# chronos-core.net
KiCad netlist of a schematic drawn in Altium Designer
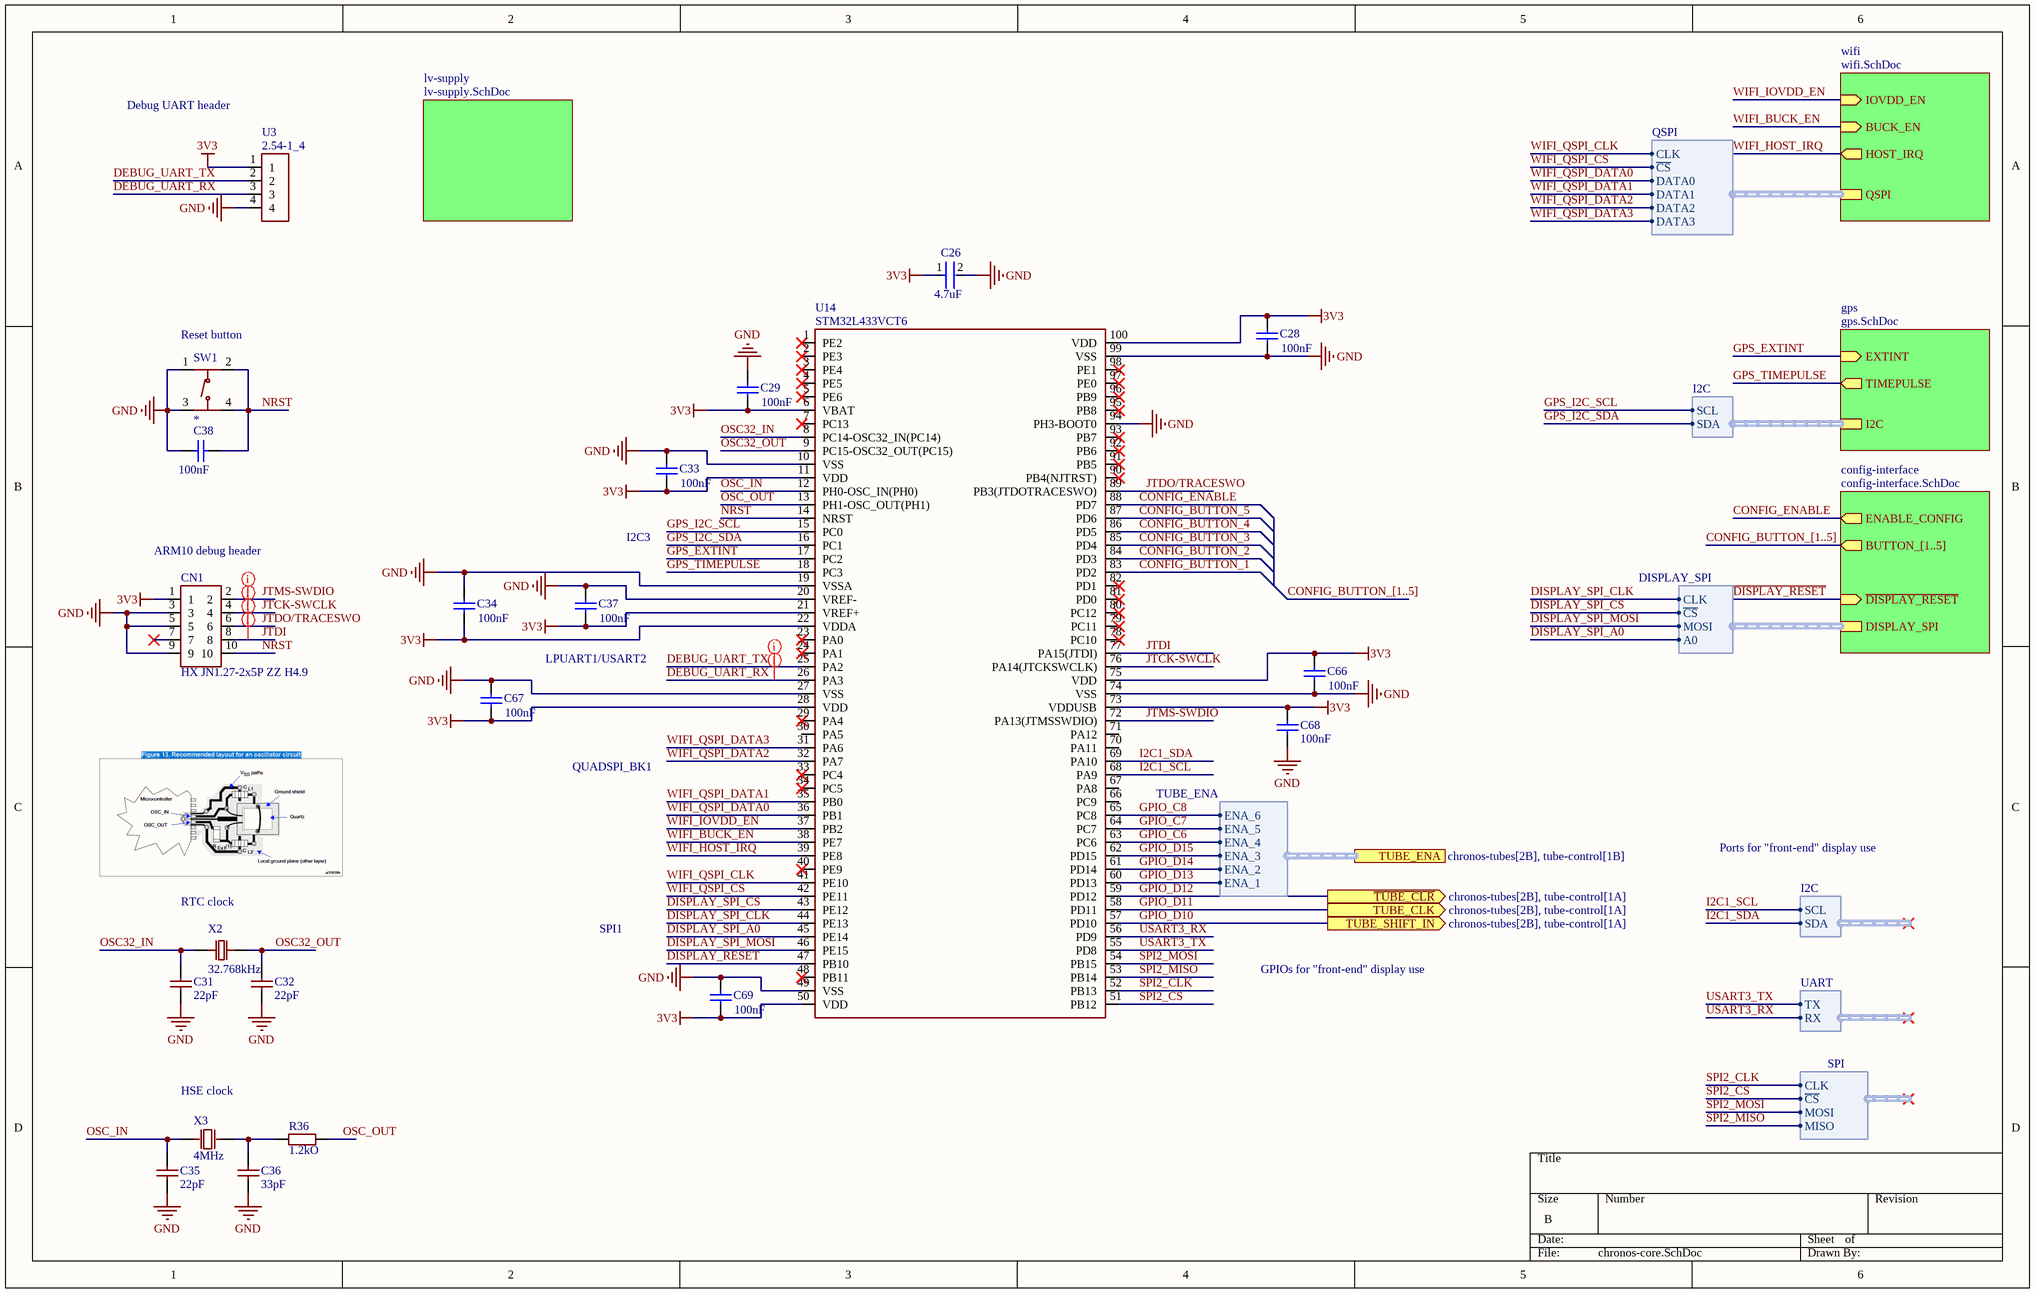
[diagram p0: chronos-core.SchDoc]

(export (version "E")
  (design (tool "Eeschema 10.0.6"))
  (components
    (comp (ref "C26")
      (value "CL05A475MP5NRNC")
      (footprint "FP-CL282-IPC_C")
      (description "Cap Ceramic 4.7uF 10V X5R ±20% SMD 0402 +85°C Paper T/R")
      (fields (field (name "CAPACITANCE") "4.7uF") (field (name "TOLERANCE") "20%"))
      (libsource (lib "Altium Content Vault") (part "b4654b650e69147ec39a6b967a45e02"))
    )
    (comp (ref "C28")
      (value "CL05B104KO5NNNC")
      (footprint "CAPC1050X55X23ML05T13")
      (description "Chip Capacitor, 100 nF, +/- 10%, 16 V, -55 to 125 degC, 0402 (1005 Metric), RoHS, Tape and Reel")
      (fields (field (name "MANUFACTURER") "Samsung Electro-Mechanics") (field (name "CAPACITANCE") "100nF"))
      (libsource (lib "Altium Content Vault") (part "CAP-NP-2"))
    )
    (comp (ref "C29")
      (value "CL05B104KO5NNNC")
      (footprint "CAPC1050X55X23ML05T13")
      (description "Chip Capacitor, 100 nF, +/- 10%, 16 V, -55 to 125 degC, 0402 (1005 Metric), RoHS, Tape and Reel")
      (fields (field (name "MANUFACTURER") "Samsung Electro-Mechanics") (field (name "CAPACITANCE") "100nF"))
      (libsource (lib "Altium Content Vault") (part "CAP-NP-2"))
    )
    (comp (ref "C31")
      (value "22pF")
      (footprint "0402CG220J500NT")
      (fields
        (field (name "JLCPCB PART #") "C1555")
        (field (name "MANUFACTURER PART NUMBER") "0402CG220J500NT")
        (field (name "MANUFACTURER") "FH (Guangdong Fenghua Advanced Tech)")
      )
      (libsource (lib "0402CG220J500NT") (part "0402CG220J500NT"))
    )
    (comp (ref "C32")
      (value "22pF")
      (footprint "0402CG220J500NT")
      (fields
        (field (name "JLCPCB PART #") "C1555")
        (field (name "MANUFACTURER PART NUMBER") "0402CG220J500NT")
        (field (name "MANUFACTURER") "FH (Guangdong Fenghua Advanced Tech)")
      )
      (libsource (lib "0402CG220J500NT") (part "0402CG220J500NT"))
    )
    (comp (ref "C33")
      (value "CL05B104KO5NNNC")
      (footprint "CAPC1050X55X23ML05T13")
      (description "Chip Capacitor, 100 nF, +/- 10%, 16 V, -55 to 125 degC, 0402 (1005 Metric), RoHS, Tape and Reel")
      (fields (field (name "MANUFACTURER") "Samsung Electro-Mechanics") (field (name "CAPACITANCE") "100nF"))
      (libsource (lib "Altium Content Vault") (part "CAP-NP-2"))
    )
    (comp (ref "C34")
      (value "CL05B104KO5NNNC")
      (footprint "CAPC1050X55X23ML05T13")
      (description "Chip Capacitor, 100 nF, +/- 10%, 16 V, -55 to 125 degC, 0402 (1005 Metric), RoHS, Tape and Reel")
      (fields (field (name "MANUFACTURER") "Samsung Electro-Mechanics") (field (name "CAPACITANCE") "100nF"))
      (libsource (lib "Altium Content Vault") (part "CAP-NP-2"))
    )
    (comp (ref "C35")
      (value "22pF")
      (footprint "0402CG220J500NT")
      (fields
        (field (name "JLCPCB PART #") "C1555")
        (field (name "MANUFACTURER PART NUMBER") "0402CG220J500NT")
        (field (name "MANUFACTURER") "FH (Guangdong Fenghua Advanced Tech)")
      )
      (libsource (lib "0402CG220J500NT") (part "0402CG220J500NT"))
    )
    (comp (ref "C36")
      (value "33pF")
      (footprint "0402CG330J500NT")
      (fields
        (field (name "JLCPCB PART #") "C1562")
        (field (name "MANUFACTURER PART NUMBER") "0402CG330J500NT")
        (field (name "MANUFACTURER") "FH (Guangdong Fenghua Advanced Tech)")
      )
      (libsource (lib "0402CG330J500NT") (part "0402CG330J500NT"))
    )
    (comp (ref "C37")
      (value "CL05B104KO5NNNC")
      (footprint "CAPC1050X55X23ML05T13")
      (description "Chip Capacitor, 100 nF, +/- 10%, 16 V, -55 to 125 degC, 0402 (1005 Metric), RoHS, Tape and Reel")
      (fields (field (name "MANUFACTURER") "Samsung Electro-Mechanics") (field (name "CAPACITANCE") "100nF"))
      (libsource (lib "Altium Content Vault") (part "CAP-NP-2"))
    )
    (comp (ref "C38")
      (value "CL05B104KO5NNNC")
      (footprint "CAPC1050X55X23ML05T13")
      (description "Chip Capacitor, 100 nF, +/- 10%, 16 V, -55 to 125 degC, 0402 (1005 Metric), RoHS, Tape and Reel")
      (fields (field (name "MANUFACTURER") "Samsung Electro-Mechanics") (field (name "CAPACITANCE") "100nF"))
      (libsource (lib "Altium Content Vault") (part "CAP-NP-2"))
    )
    (comp (ref "C66")
      (value "CL05B104KO5NNNC")
      (footprint "CAPC1050X55X23ML05T13")
      (description "Chip Capacitor, 100 nF, +/- 10%, 16 V, -55 to 125 degC, 0402 (1005 Metric), RoHS, Tape and Reel")
      (fields (field (name "MANUFACTURER") "Samsung Electro-Mechanics") (field (name "CAPACITANCE") "100nF"))
      (libsource (lib "Altium Content Vault") (part "CAP-NP-2"))
    )
    (comp (ref "C67")
      (value "CL05B104KO5NNNC")
      (footprint "CAPC1050X55X23ML05T13")
      (description "Chip Capacitor, 100 nF, +/- 10%, 16 V, -55 to 125 degC, 0402 (1005 Metric), RoHS, Tape and Reel")
      (fields (field (name "MANUFACTURER") "Samsung Electro-Mechanics") (field (name "CAPACITANCE") "100nF"))
      (libsource (lib "Altium Content Vault") (part "CAP-NP-2"))
    )
    (comp (ref "C68")
      (value "CL05B104KO5NNNC")
      (footprint "CAPC1050X55X23ML05T13")
      (description "Chip Capacitor, 100 nF, +/- 10%, 16 V, -55 to 125 degC, 0402 (1005 Metric), RoHS, Tape and Reel")
      (fields (field (name "MANUFACTURER") "Samsung Electro-Mechanics") (field (name "CAPACITANCE") "100nF"))
      (libsource (lib "Altium Content Vault") (part "CAP-NP-2"))
    )
    (comp (ref "C69")
      (value "CL05B104KO5NNNC")
      (footprint "CAPC1050X55X23ML05T13")
      (description "Chip Capacitor, 100 nF, +/- 10%, 16 V, -55 to 125 degC, 0402 (1005 Metric), RoHS, Tape and Reel")
      (fields (field (name "MANUFACTURER") "Samsung Electro-Mechanics") (field (name "CAPACITANCE") "100nF"))
      (libsource (lib "Altium Content Vault") (part "CAP-NP-2"))
    )
    (comp (ref "CN1")
      (value "HX JN1.27-2x5P ZZ H4.9")
      (footprint "HX JN1.27-2x5P ZZ H4.9")
      (fields (field (name "JLCPCB PART #") "C42372547") (field (name "MANUFACTURER") "hanxia"))
      (libsource (lib "HX JN1.27-2x5P ZZ H4.9") (part "HX JN1.27-2x5P ZZ H4.9"))
    )
    (comp (ref "R36")
      (value "1.2kO")
      (footprint "0402WGF1201TCE")
      (fields
        (field (name "JLCPCB PART #") "C25862")
        (field (name "MANUFACTURER PART NUMBER") "0402WGF1201TCE")
        (field (name "MANUFACTURER") "UNI-ROYAL(Uniroyal Elec)")
      )
      (libsource (lib "0402WGF1201TCE") (part "0402WGF1201TCE"))
    )
    (comp (ref "SW1")
      (value "TS-1187A-B-A-B")
      (footprint "TS-1187A-B-A-B")
      (fields
        (field (name "ALTIUM_VALUE") "*")
        (field (name "JLCPCB PART #") "C318884")
        (field (name "MANUFACTURER") "XKB Connection")
      )
      (libsource (lib "TS-1187A-B-A-B") (part "TS-1187A-B-A-B"))
    )
    (comp (ref "U3")
      (value "2.54-1_4")
      (footprint "2.54-1_4")
      (fields
        (field (name "JLCPCB PART #") "C5116483")
        (field (name "MANUFACTURER PART NUMBER") "2.54-1*4")
        (field (name "MANUFACTURER") "ZHOURI")
      )
      (libsource (lib "2.54-1_4") (part "2.54-1_4"))
    )
    (comp (ref "U14")
      (value "STM32L433VCT6")
      (footprint "STM32L433VCT6")
      (fields (field (name "JLCPCB PART #") "C915966") (field (name "MANUFACTURER") "STMicroelectronics"))
      (libsource (lib "STM32L433VCT6") (part "STM32L433VCT6"))
    )
    (comp (ref "X2")
      (value "32.768kHz")
      (footprint "Q13FC13500004")
      (description "Crystals. -40C~+85C 12.5pF 32.768kHz 70kohm Crystal Oscillator +/-20ppm SMD3215-2P Crystals ROHS")
      (fields
        (field (name "JLCPCB PART #") "C32346")
        (field (name "MANUFACTURER PART NUMBER") "Q13FC13500004")
      )
      (libsource (lib "Q13FC13500004") (part "Q13FC13500004"))
    )
    (comp (ref "X3")
      (value "4MHz")
      (footprint "X49SM4MSD2SC")
      (description "Crystals. -20C~+70C 120ohm 20pF 4MHz Crystal Oscillator +/-20ppm +/-30ppm HC-49S-SMD Crystals ROHS")
      (fields
        (field (name "JLCPCB PART #") "C13774")
        (field (name "MANUFACTURER PART NUMBER") "X49SM4MSD2SC")
      )
      (libsource (lib "X49SM4MSD2SC") (part "X49SM4MSD2SC"))
    )
  )
  (nets
    (net (code "7") (name "/CONFIG_BUTTON_1") (class "Default")
      (node (ref "U14") (pin "83") (pinfunction "PD2_83") (pintype "passive"))
    )
    (net (code "8") (name "/CONFIG_BUTTON_2") (class "Default")
      (node (ref "U14") (pin "84") (pinfunction "PD3_84") (pintype "passive"))
    )
    (net (code "9") (name "/CONFIG_BUTTON_3") (class "Default")
      (node (ref "U14") (pin "85") (pinfunction "PD4_85") (pintype "passive"))
    )
    (net (code "10") (name "/CONFIG_BUTTON_4") (class "Default")
      (node (ref "U14") (pin "86") (pinfunction "PD5_86") (pintype "passive"))
    )
    (net (code "11") (name "/CONFIG_BUTTON_5") (class "Default")
      (node (ref "U14") (pin "87") (pinfunction "PD6_87") (pintype "passive"))
    )
    (net (code "13") (name "/CONFIG_ENABLE") (class "Default")
      (node (ref "U14") (pin "88") (pinfunction "PD7_88") (pintype "passive"))
    )
    (net (code "14") (name "/DEBUG_UART_RX") (class "Default")
      (node (ref "U14") (pin "26") (pinfunction "PA3_26") (pintype "passive"))
      (node (ref "U3") (pin "3") (pinfunction "3_3") (pintype "passive"))
    )
    (net (code "15") (name "/DEBUG_UART_TX") (class "Default")
      (node (ref "U14") (pin "25") (pinfunction "PA2_25") (pintype "passive"))
      (node (ref "U3") (pin "2") (pinfunction "2_2") (pintype "passive"))
    )
    (net (code "16") (name "/DISPLAY_RESET") (class "Default")
      (node (ref "U14") (pin "47") (pinfunction "PB10_47") (pintype "passive"))
    )
    (net (code "17") (name "/DISPLAY_SPI_A0") (class "Default")
      (node (ref "U14") (pin "45") (pinfunction "PE14_45") (pintype "passive"))
    )
    (net (code "18") (name "/DISPLAY_SPI_CLK") (class "Default")
      (node (ref "U14") (pin "44") (pinfunction "PE13_44") (pintype "passive"))
    )
    (net (code "19") (name "/DISPLAY_SPI_CS") (class "Default")
      (node (ref "U14") (pin "43") (pinfunction "PE12_43") (pintype "passive"))
    )
    (net (code "20") (name "/DISPLAY_SPI_MOSI") (class "Default")
      (node (ref "U14") (pin "46") (pinfunction "PE15_46") (pintype "passive"))
    )
    (net (code "21") (name "/GPIO_C6") (class "Default")
      (node (ref "U14") (pin "63") (pinfunction "PC6_63") (pintype "passive"))
    )
    (net (code "22") (name "/GPIO_C7") (class "Default")
      (node (ref "U14") (pin "64") (pinfunction "PC7_64") (pintype "passive"))
    )
    (net (code "23") (name "/GPIO_C8") (class "Default")
      (node (ref "U14") (pin "65") (pinfunction "PC8_65") (pintype "passive"))
    )
    (net (code "24") (name "/GPIO_D10") (class "Default")
      (node (ref "U14") (pin "57") (pinfunction "PD10_57") (pintype "passive"))
    )
    (net (code "25") (name "/GPIO_D11") (class "Default")
      (node (ref "U14") (pin "58") (pinfunction "PD11_58") (pintype "passive"))
    )
    (net (code "26") (name "/GPIO_D12") (class "Default")
      (node (ref "U14") (pin "59") (pinfunction "PD12_59") (pintype "passive"))
    )
    (net (code "27") (name "/GPIO_D13") (class "Default")
      (node (ref "U14") (pin "60") (pinfunction "PD13_60") (pintype "passive"))
    )
    (net (code "28") (name "/GPIO_D14") (class "Default")
      (node (ref "U14") (pin "61") (pinfunction "PD14_61") (pintype "passive"))
    )
    (net (code "29") (name "/GPIO_D15") (class "Default")
      (node (ref "U14") (pin "62") (pinfunction "PD15_62") (pintype "passive"))
    )
    (net (code "30") (name "/GPS_EXTINT") (class "Default")
      (node (ref "U14") (pin "17") (pinfunction "PC2_17") (pintype "passive"))
    )
    (net (code "31") (name "/GPS_I2C_SCL") (class "Default")
      (node (ref "U14") (pin "15") (pinfunction "PC0_15") (pintype "passive"))
    )
    (net (code "32") (name "/GPS_I2C_SDA") (class "Default")
      (node (ref "U14") (pin "16") (pinfunction "PC1_16") (pintype "passive"))
    )
    (net (code "33") (name "/GPS_TIMEPULSE") (class "Default")
      (node (ref "U14") (pin "18") (pinfunction "PC3_18") (pintype "passive"))
    )
    (net (code "34") (name "/I2C1_SCL") (class "Default")
      (node (ref "U14") (pin "68") (pinfunction "PA9_68") (pintype "passive"))
    )
    (net (code "35") (name "/I2C1_SDA") (class "Default")
      (node (ref "U14") (pin "69") (pinfunction "PA10_69") (pintype "passive"))
    )
    (net (code "36") (name "/JTCK-SWCLK") (class "Default")
      (node (ref "CN1") (pin "4") (pinfunction "4_4") (pintype "passive"))
      (node (ref "U14") (pin "76") (pinfunction "PA14(JTCKSWCLK)_76") (pintype "passive"))
    )
    (net (code "37") (name "/JTDI") (class "Default")
      (node (ref "CN1") (pin "8") (pinfunction "8_8") (pintype "passive"))
      (node (ref "U14") (pin "77") (pinfunction "PA15(JTDI)_77") (pintype "passive"))
    )
    (net (code "38") (name "/JTDO{slash}TRACESWO") (class "Default")
      (node (ref "CN1") (pin "6") (pinfunction "6_6") (pintype "passive"))
      (node (ref "U14") (pin "89") (pinfunction "PB3(JTDOTRACESWO)_89") (pintype "passive"))
    )
    (net (code "39") (name "/JTMS-SWDIO") (class "Default")
      (node (ref "CN1") (pin "2") (pinfunction "2_2") (pintype "passive"))
      (node (ref "U14") (pin "72") (pinfunction "PA13(JTMSSWDIO)_72") (pintype "passive"))
    )
    (net (code "40") (name "/NRST") (class "Default")
      (node (ref "C38") (pin "1") (pinfunction "1_1") (pintype "passive"))
      (node (ref "CN1") (pin "10") (pinfunction "10_10") (pintype "passive"))
      (node (ref "SW1") (pin "2") (pinfunction "B_2") (pintype "passive"))
      (node (ref "SW1") (pin "4") (pinfunction "D_4") (pintype "passive"))
      (node (ref "U14") (pin "14") (pinfunction "NRST_14") (pintype "passive"))
    )
    (net (code "41") (name "/OSC32_IN") (class "Default")
      (node (ref "C31") (pin "2") (pinfunction "2_2") (pintype "passive"))
      (node (ref "U14") (pin "8") (pinfunction "PC14-OSC32_IN(PC14)_8") (pintype "passive"))
      (node (ref "X2") (pin "2") (pinfunction "2_2") (pintype "passive"))
    )
    (net (code "42") (name "/OSC32_OUT") (class "Default")
      (node (ref "C32") (pin "2") (pinfunction "2_2") (pintype "passive"))
      (node (ref "U14") (pin "9") (pinfunction "PC15-OSC32_OUT(PC15)_9") (pintype "passive"))
      (node (ref "X2") (pin "1") (pinfunction "1_1") (pintype "passive"))
    )
    (net (code "43") (name "/OSC_IN") (class "Default")
      (node (ref "C35") (pin "2") (pinfunction "2_2") (pintype "passive"))
      (node (ref "U14") (pin "12") (pinfunction "PH0-OSC_IN(PH0)_12") (pintype "passive"))
      (node (ref "X3") (pin "1") (pinfunction "OSC1_1") (pintype "passive"))
    )
    (net (code "44") (name "/OSC_OUT") (class "Default")
      (node (ref "R36") (pin "2") (pinfunction "2_2") (pintype "passive"))
      (node (ref "U14") (pin "13") (pinfunction "PH1-OSC_OUT(PH1)_13") (pintype "passive"))
    )
    (net (code "45") (name "/SPI2_CLK") (class "Default")
      (node (ref "U14") (pin "52") (pinfunction "PB13_52") (pintype "passive"))
    )
    (net (code "46") (name "/SPI2_CS") (class "Default")
      (node (ref "U14") (pin "51") (pinfunction "PB12_51") (pintype "passive"))
    )
    (net (code "47") (name "/SPI2_MISO") (class "Default")
      (node (ref "U14") (pin "53") (pinfunction "PB14_53") (pintype "passive"))
    )
    (net (code "48") (name "/SPI2_MOSI") (class "Default")
      (node (ref "U14") (pin "54") (pinfunction "PB15_54") (pintype "passive"))
    )
    (net (code "49") (name "/USART3_RX") (class "Default")
      (node (ref "U14") (pin "56") (pinfunction "PD9_56") (pintype "passive"))
    )
    (net (code "50") (name "/USART3_TX") (class "Default")
      (node (ref "U14") (pin "55") (pinfunction "PD8_55") (pintype "passive"))
    )
    (net (code "51") (name "/WIFI_BUCK_EN") (class "Default")
      (node (ref "U14") (pin "38") (pinfunction "PE7_38") (pintype "passive"))
    )
    (net (code "52") (name "/WIFI_HOST_IRQ") (class "Default")
      (node (ref "U14") (pin "39") (pinfunction "PE8_39") (pintype "passive"))
    )
    (net (code "53") (name "/WIFI_IOVDD_EN") (class "Default")
      (node (ref "U14") (pin "37") (pinfunction "PB2_37") (pintype "passive"))
    )
    (net (code "54") (name "/WIFI_QSPI_CLK") (class "Default")
      (node (ref "U14") (pin "41") (pinfunction "PE10_41") (pintype "passive"))
    )
    (net (code "55") (name "/WIFI_QSPI_CS") (class "Default")
      (node (ref "U14") (pin "42") (pinfunction "PE11_42") (pintype "passive"))
    )
    (net (code "56") (name "/WIFI_QSPI_DATA0") (class "Default")
      (node (ref "U14") (pin "36") (pinfunction "PB1_36") (pintype "passive"))
    )
    (net (code "57") (name "/WIFI_QSPI_DATA1") (class "Default")
      (node (ref "U14") (pin "35") (pinfunction "PB0_35") (pintype "passive"))
    )
    (net (code "58") (name "/WIFI_QSPI_DATA2") (class "Default")
      (node (ref "U14") (pin "32") (pinfunction "PA7_32") (pintype "passive"))
    )
    (net (code "59") (name "/WIFI_QSPI_DATA3") (class "Default")
      (node (ref "U14") (pin "31") (pinfunction "PA6_31") (pintype "passive"))
    )
    (net (code "66") (name "3V3") (class "Default")
      (node (ref "C26") (pin "1") (pinfunction "1_1") (pintype "passive"))
      (node (ref "C28") (pin "1") (pinfunction "1_1") (pintype "passive"))
      (node (ref "C29") (pin "1") (pinfunction "1_1") (pintype "passive"))
      (node (ref "C33") (pin "1") (pinfunction "1_1") (pintype "passive"))
      (node (ref "C34") (pin "1") (pinfunction "1_1") (pintype "passive"))
      (node (ref "C37") (pin "1") (pinfunction "1_1") (pintype "passive"))
      (node (ref "C66") (pin "1") (pinfunction "1_1") (pintype "passive"))
      (node (ref "C67") (pin "1") (pinfunction "1_1") (pintype "passive"))
      (node (ref "C68") (pin "1") (pinfunction "1_1") (pintype "passive"))
      (node (ref "C69") (pin "1") (pinfunction "1_1") (pintype "passive"))
      (node (ref "CN1") (pin "1") (pinfunction "1_1") (pintype "passive"))
      (node (ref "U14") (pin "100") (pinfunction "VDD_100") (pintype "passive"))
      (node (ref "U14") (pin "11") (pinfunction "VDD_11") (pintype "passive"))
      (node (ref "U14") (pin "21") (pinfunction "VREF+_21") (pintype "passive"))
      (node (ref "U14") (pin "22") (pinfunction "VDDA_22") (pintype "passive"))
      (node (ref "U14") (pin "28") (pinfunction "VDD_28") (pintype "passive"))
      (node (ref "U14") (pin "50") (pinfunction "VDD_50") (pintype "passive"))
      (node (ref "U14") (pin "6") (pinfunction "VBAT_6") (pintype "passive"))
      (node (ref "U14") (pin "73") (pinfunction "VDDUSB_73") (pintype "passive"))
      (node (ref "U14") (pin "75") (pinfunction "VDD_75") (pintype "passive"))
      (node (ref "U3") (pin "1") (pinfunction "1_1") (pintype "passive"))
    )
    (net (code "67") (name "GND") (class "Default")
      (node (ref "C26") (pin "2") (pinfunction "2_2") (pintype "passive"))
      (node (ref "C28") (pin "2") (pinfunction "2_2") (pintype "passive"))
      (node (ref "C29") (pin "2") (pinfunction "2_2") (pintype "passive"))
      (node (ref "C31") (pin "1") (pinfunction "1_1") (pintype "passive"))
      (node (ref "C32") (pin "1") (pinfunction "1_1") (pintype "passive"))
      (node (ref "C33") (pin "2") (pinfunction "2_2") (pintype "passive"))
      (node (ref "C34") (pin "2") (pinfunction "2_2") (pintype "passive"))
      (node (ref "C35") (pin "1") (pinfunction "1_1") (pintype "passive"))
      (node (ref "C36") (pin "1") (pinfunction "1_1") (pintype "passive"))
      (node (ref "C37") (pin "2") (pinfunction "2_2") (pintype "passive"))
      (node (ref "C38") (pin "2") (pinfunction "2_2") (pintype "passive"))
      (node (ref "C66") (pin "2") (pinfunction "2_2") (pintype "passive"))
      (node (ref "C67") (pin "2") (pinfunction "2_2") (pintype "passive"))
      (node (ref "C68") (pin "2") (pinfunction "2_2") (pintype "passive"))
      (node (ref "C69") (pin "2") (pinfunction "2_2") (pintype "passive"))
      (node (ref "CN1") (pin "3") (pinfunction "3_3") (pintype "passive"))
      (node (ref "CN1") (pin "5") (pinfunction "5_5") (pintype "passive"))
      (node (ref "CN1") (pin "9") (pinfunction "9_9") (pintype "passive"))
      (node (ref "SW1") (pin "1") (pinfunction "A_1") (pintype "passive"))
      (node (ref "SW1") (pin "3") (pinfunction "C_3") (pintype "passive"))
      (node (ref "U14") (pin "10") (pinfunction "VSS_10") (pintype "passive"))
      (node (ref "U14") (pin "19") (pinfunction "VSSA_19") (pintype "passive"))
      (node (ref "U14") (pin "20") (pinfunction "VREF-_20") (pintype "passive"))
      (node (ref "U14") (pin "27") (pinfunction "VSS_27") (pintype "passive"))
      (node (ref "U14") (pin "49") (pinfunction "VSS_49") (pintype "passive"))
      (node (ref "U14") (pin "74") (pinfunction "VSS_74") (pintype "passive"))
      (node (ref "U14") (pin "94") (pinfunction "PH3-BOOT0_94") (pintype "passive"))
      (node (ref "U14") (pin "99") (pinfunction "VSS_99") (pintype "passive"))
      (node (ref "U3") (pin "4") (pinfunction "4_4") (pintype "passive"))
    )
    (net (code "68") (name "Net-(X3-OSC2)") (class "Default")
      (node (ref "C36") (pin "2") (pinfunction "2_2") (pintype "passive"))
      (node (ref "R36") (pin "1") (pinfunction "1_1") (pintype "passive"))
      (node (ref "X3") (pin "2") (pinfunction "OSC2_2") (pintype "passive"))
    )
    (net (code "69") (name "unconnected-(CN1-Pad7)") (class "Default")
      (node (ref "CN1") (pin "7") (pinfunction "7_7") (pintype "passive+no_connect"))
    )
    (net (code "70") (name "unconnected-(U14-PA0-Pad23)") (class "Default")
      (node (ref "U14") (pin "23") (pinfunction "PA0_23") (pintype "passive+no_connect"))
    )
    (net (code "71") (name "unconnected-(U14-PA1-Pad24)") (class "Default")
      (node (ref "U14") (pin "24") (pinfunction "PA1_24") (pintype "passive+no_connect"))
    )
    (net (code "72") (name "unconnected-(U14-PA4-Pad29)") (class "Default")
      (node (ref "U14") (pin "29") (pinfunction "PA4_29") (pintype "passive+no_connect"))
    )
    (net (code "73") (name "unconnected-(U14-PA5-Pad30)") (class "Default")
      (node (ref "U14") (pin "30") (pinfunction "PA5_30") (pintype "passive"))
    )
    (net (code "74") (name "unconnected-(U14-PA8-Pad67)") (class "Default")
      (node (ref "U14") (pin "67") (pinfunction "PA8_67") (pintype "passive"))
    )
    (net (code "75") (name "unconnected-(U14-PA11-Pad70)") (class "Default")
      (node (ref "U14") (pin "70") (pinfunction "PA11_70") (pintype "passive"))
    )
    (net (code "76") (name "unconnected-(U14-PA12-Pad71)") (class "Default")
      (node (ref "U14") (pin "71") (pinfunction "PA12_71") (pintype "passive"))
    )
    (net (code "77") (name "unconnected-(U14-PB4(NJTRST)-Pad90)") (class "Default")
      (node (ref "U14") (pin "90") (pinfunction "PB4(NJTRST)_90") (pintype "passive+no_connect"))
    )
    (net (code "78") (name "unconnected-(U14-PB5-Pad91)") (class "Default")
      (node (ref "U14") (pin "91") (pinfunction "PB5_91") (pintype "passive+no_connect"))
    )
    (net (code "79") (name "unconnected-(U14-PB6-Pad92)") (class "Default")
      (node (ref "U14") (pin "92") (pinfunction "PB6_92") (pintype "passive+no_connect"))
    )
    (net (code "80") (name "unconnected-(U14-PB7-Pad93)") (class "Default")
      (node (ref "U14") (pin "93") (pinfunction "PB7_93") (pintype "passive+no_connect"))
    )
    (net (code "81") (name "unconnected-(U14-PB8-Pad95)") (class "Default")
      (node (ref "U14") (pin "95") (pinfunction "PB8_95") (pintype "passive+no_connect"))
    )
    (net (code "82") (name "unconnected-(U14-PB9-Pad96)") (class "Default")
      (node (ref "U14") (pin "96") (pinfunction "PB9_96") (pintype "passive+no_connect"))
    )
    (net (code "83") (name "unconnected-(U14-PB11-Pad48)") (class "Default")
      (node (ref "U14") (pin "48") (pinfunction "PB11_48") (pintype "passive+no_connect"))
    )
    (net (code "84") (name "unconnected-(U14-PC4-Pad33)") (class "Default")
      (node (ref "U14") (pin "33") (pinfunction "PC4_33") (pintype "passive+no_connect"))
    )
    (net (code "85") (name "unconnected-(U14-PC5-Pad34)") (class "Default")
      (node (ref "U14") (pin "34") (pinfunction "PC5_34") (pintype "passive+no_connect"))
    )
    (net (code "86") (name "unconnected-(U14-PC9-Pad66)") (class "Default")
      (node (ref "U14") (pin "66") (pinfunction "PC9_66") (pintype "passive"))
    )
    (net (code "87") (name "unconnected-(U14-PC10-Pad78)") (class "Default")
      (node (ref "U14") (pin "78") (pinfunction "PC10_78") (pintype "passive+no_connect"))
    )
    (net (code "88") (name "unconnected-(U14-PC11-Pad79)") (class "Default")
      (node (ref "U14") (pin "79") (pinfunction "PC11_79") (pintype "passive+no_connect"))
    )
    (net (code "89") (name "unconnected-(U14-PC12-Pad80)") (class "Default")
      (node (ref "U14") (pin "80") (pinfunction "PC12_80") (pintype "passive+no_connect"))
    )
    (net (code "90") (name "unconnected-(U14-PC13-Pad7)") (class "Default")
      (node (ref "U14") (pin "7") (pinfunction "PC13_7") (pintype "passive+no_connect"))
    )
    (net (code "91") (name "unconnected-(U14-PD0-Pad81)") (class "Default")
      (node (ref "U14") (pin "81") (pinfunction "PD0_81") (pintype "passive+no_connect"))
    )
    (net (code "92") (name "unconnected-(U14-PD1-Pad82)") (class "Default")
      (node (ref "U14") (pin "82") (pinfunction "PD1_82") (pintype "passive+no_connect"))
    )
    (net (code "93") (name "unconnected-(U14-PE0-Pad97)") (class "Default")
      (node (ref "U14") (pin "97") (pinfunction "PE0_97") (pintype "passive+no_connect"))
    )
    (net (code "94") (name "unconnected-(U14-PE1-Pad98)") (class "Default")
      (node (ref "U14") (pin "98") (pinfunction "PE1_98") (pintype "passive+no_connect"))
    )
    (net (code "95") (name "unconnected-(U14-PE2-Pad1)") (class "Default")
      (node (ref "U14") (pin "1") (pinfunction "PE2_1") (pintype "passive+no_connect"))
    )
    (net (code "96") (name "unconnected-(U14-PE3-Pad2)") (class "Default")
      (node (ref "U14") (pin "2") (pinfunction "PE3_2") (pintype "passive+no_connect"))
    )
    (net (code "97") (name "unconnected-(U14-PE4-Pad3)") (class "Default")
      (node (ref "U14") (pin "3") (pinfunction "PE4_3") (pintype "passive+no_connect"))
    )
    (net (code "98") (name "unconnected-(U14-PE5-Pad4)") (class "Default")
      (node (ref "U14") (pin "4") (pinfunction "PE5_4") (pintype "passive+no_connect"))
    )
    (net (code "99") (name "unconnected-(U14-PE6-Pad5)") (class "Default")
      (node (ref "U14") (pin "5") (pinfunction "PE6_5") (pintype "passive+no_connect"))
    )
    (net (code "100") (name "unconnected-(U14-PE9-Pad40)") (class "Default")
      (node (ref "U14") (pin "40") (pinfunction "PE9_40") (pintype "passive+no_connect"))
    )
  )
)
